# SMPS.net
KiCad netlist of a schematic drawn in Altium Designer
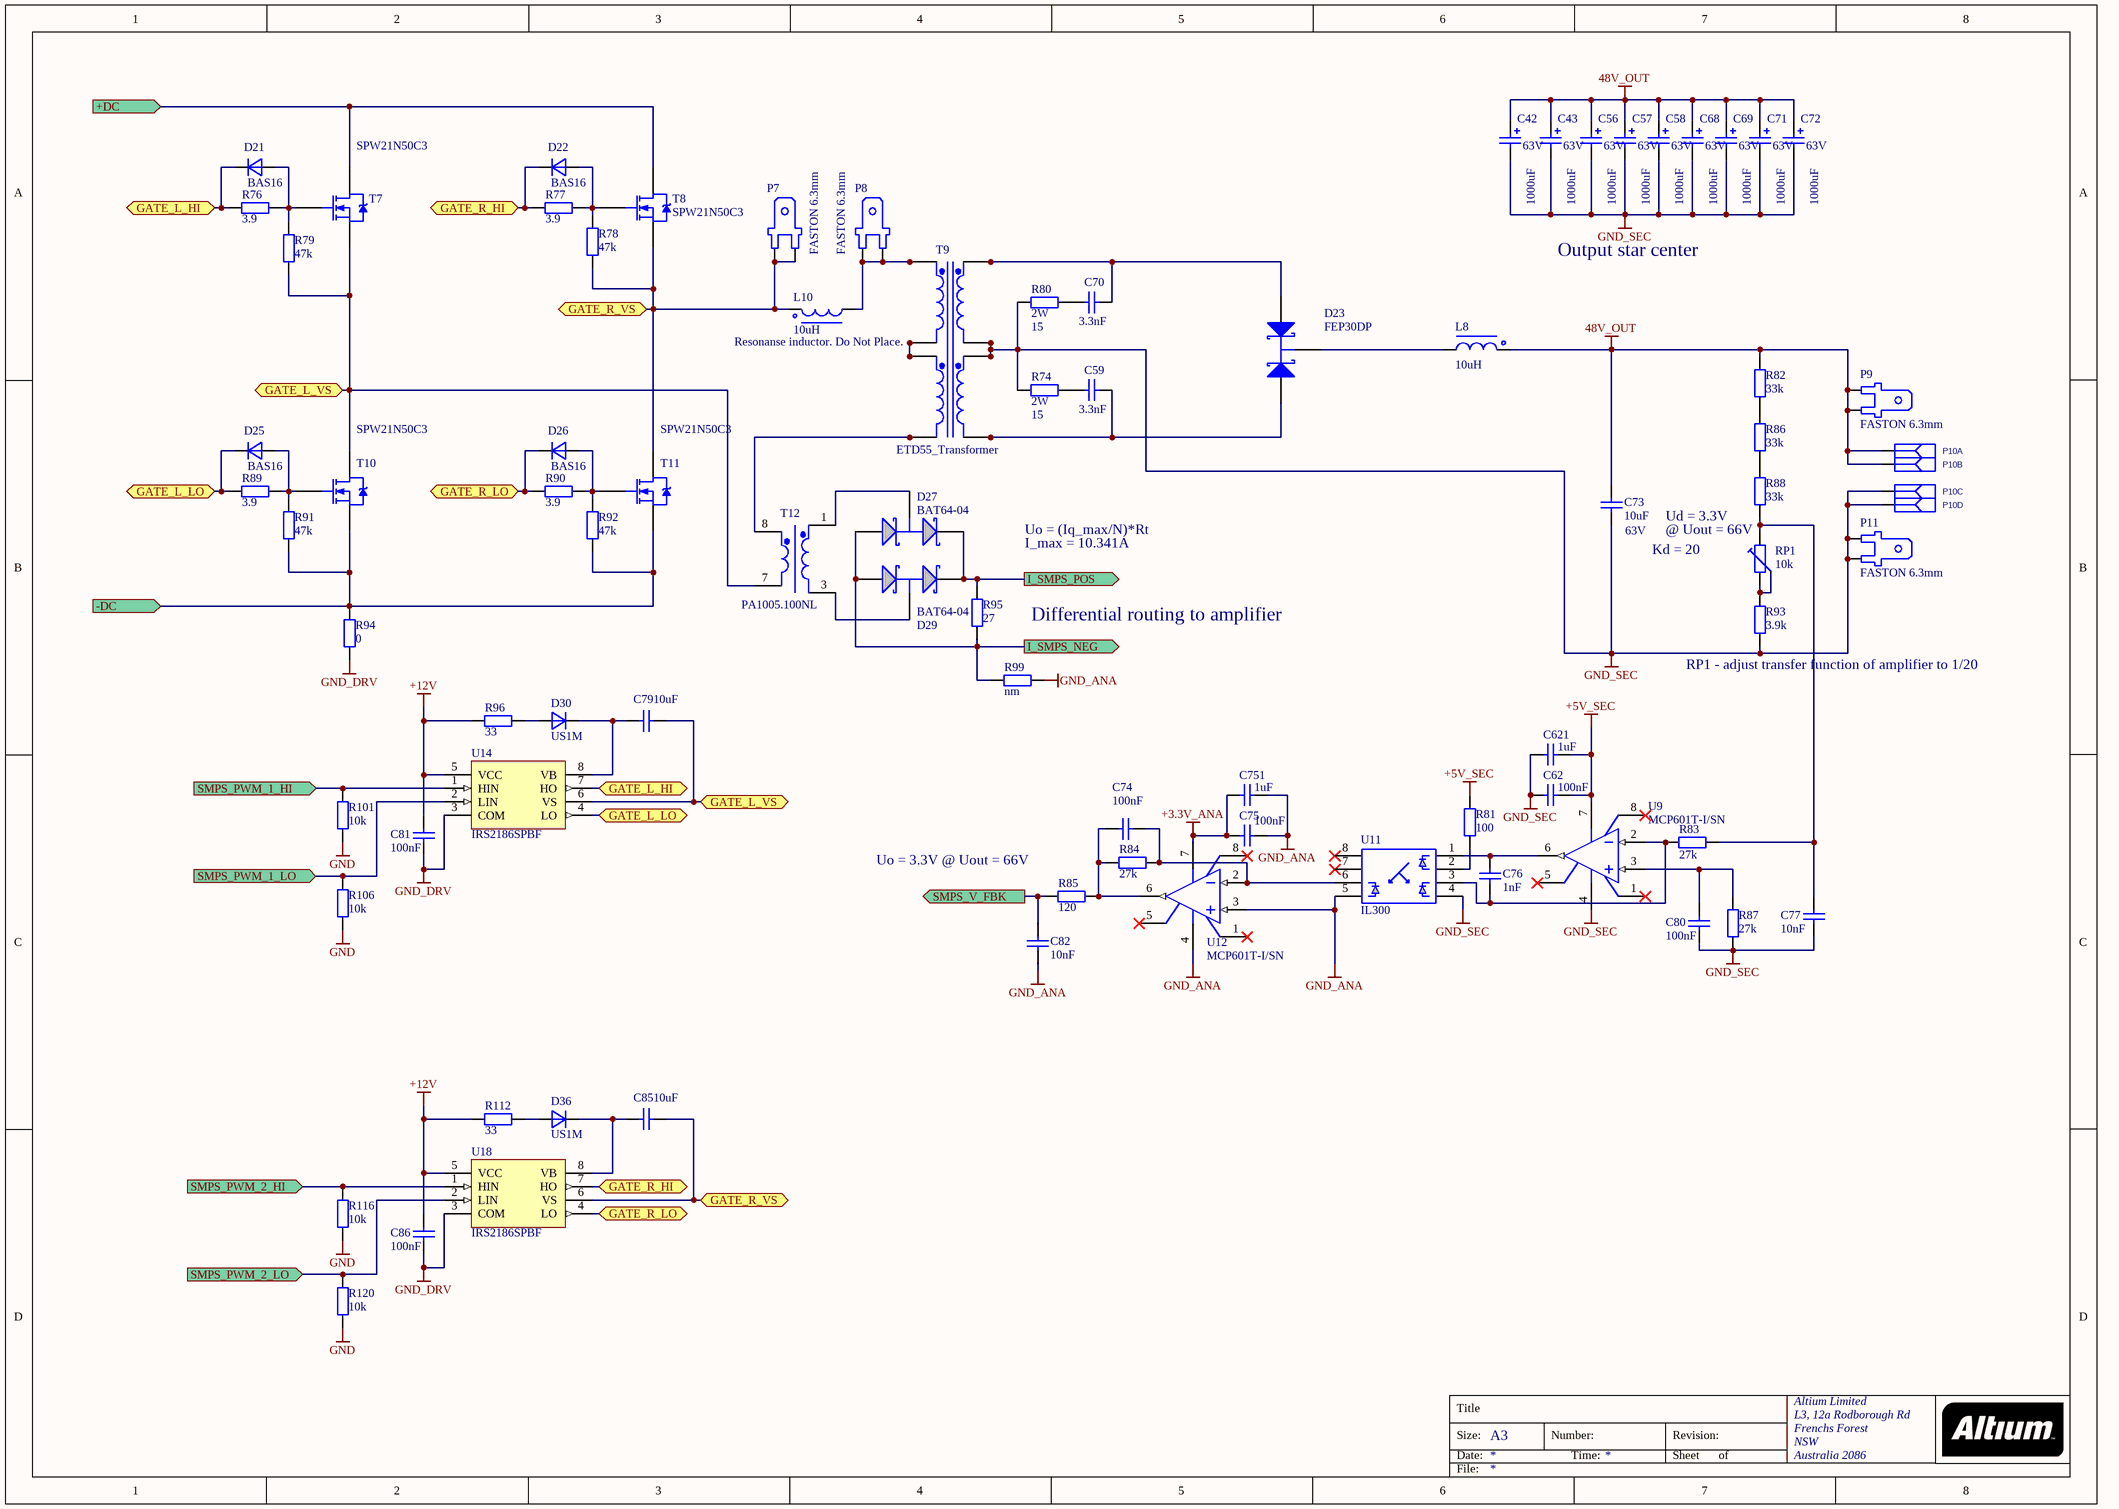
[diagram p0: SMPS.SchDoc]

(export (version "E")
  (design (tool "Eeschema 10.0.6"))
  (components
    (comp (ref "C42")
      (value "1000uF")
      (footprint "CAPPR7.5-18x35.5")
      (fields (field (name "VOLTAGE") "63V") (field (name "Comment") "Cap"))
      (libsource (lib "Capacitors") (part "Cap pol"))
    )
    (comp (ref "C43")
      (value "1000uF")
      (footprint "CAPPR7.5-18x35.5")
      (fields (field (name "VOLTAGE") "63V") (field (name "Comment") "Cap"))
      (libsource (lib "Capacitors") (part "Cap pol"))
    )
    (comp (ref "C56")
      (value "1000uF")
      (footprint "CAPPR7.5-18x35.5")
      (fields (field (name "VOLTAGE") "63V") (field (name "Comment") "Cap"))
      (libsource (lib "Capacitors") (part "Cap pol"))
    )
    (comp (ref "C57")
      (value "1000uF")
      (footprint "CAPPR7.5-18x35.5")
      (fields (field (name "VOLTAGE") "63V") (field (name "Comment") "Cap"))
      (libsource (lib "Capacitors") (part "Cap pol"))
    )
    (comp (ref "C58")
      (value "1000uF")
      (footprint "CAPPR7.5-18x35.5")
      (fields (field (name "VOLTAGE") "63V") (field (name "Comment") "Cap"))
      (libsource (lib "Capacitors") (part "Cap pol"))
    )
    (comp (ref "C59")
      (value "3.3nF")
      (footprint "CAP26X19P22_5H")
      (fields (field (name "Comment") "Cap"))
      (libsource (lib "Capacitors") (part "Cap"))
    )
    (comp (ref "C62")
      (value "100nF")
      (footprint "1206_REFLOW")
      (fields (field (name "Comment") "Cap 1206"))
      (libsource (lib "Capacitors") (part "Cap 1206"))
    )
    (comp (ref "C68")
      (value "1000uF")
      (footprint "CAPPR7.5-18x35.5")
      (fields (field (name "VOLTAGE") "63V") (field (name "Comment") "Cap"))
      (libsource (lib "Capacitors") (part "Cap pol"))
    )
    (comp (ref "C69")
      (value "1000uF")
      (footprint "CAPPR7.5-18x35.5")
      (fields (field (name "VOLTAGE") "63V") (field (name "Comment") "Cap"))
      (libsource (lib "Capacitors") (part "Cap pol"))
    )
    (comp (ref "C70")
      (value "3.3nF")
      (footprint "CAP26X19P22_5H")
      (fields (field (name "Comment") "Cap"))
      (libsource (lib "Capacitors") (part "Cap"))
    )
    (comp (ref "C71")
      (value "1000uF")
      (footprint "CAPPR7.5-18x35.5")
      (fields (field (name "VOLTAGE") "63V") (field (name "Comment") "Cap"))
      (libsource (lib "Capacitors") (part "Cap pol"))
    )
    (comp (ref "C72")
      (value "1000uF")
      (footprint "CAPPR7.5-18x35.5")
      (fields (field (name "VOLTAGE") "63V") (field (name "Comment") "Cap"))
      (libsource (lib "Capacitors") (part "Cap pol"))
    )
    (comp (ref "C73")
      (value "10uF")
      (footprint "RECT 26.5X8.5 RM22.5")
      (fields
        (field (name "VOLTAGE") "63V")
        (field (name "MANUFACTURER") "WIMA")
        (field (name "Comment") "Cap")
      )
      (libsource (lib "Capacitors") (part "Cap"))
    )
    (comp (ref "C74")
      (value "100nF")
      (footprint "1206_REFLOW")
      (fields (field (name "Comment") "Cap 1206"))
      (libsource (lib "Capacitors") (part "Cap 1206"))
    )
    (comp (ref "C75")
      (value "100nF")
      (footprint "1206_REFLOW")
      (fields (field (name "Comment") "Cap 1206"))
      (libsource (lib "Capacitors") (part "Cap 1206"))
    )
    (comp (ref "C76")
      (value "1nF")
      (footprint "1206_REFLOW")
      (fields (field (name "Comment") "Cap 1206"))
      (libsource (lib "Capacitors") (part "Cap 1206"))
    )
    (comp (ref "C77")
      (value "10nF")
      (footprint "1206_REFLOW")
      (fields (field (name "Comment") "Cap 1206"))
      (libsource (lib "Capacitors") (part "Cap 1206"))
    )
    (comp (ref "C79")
      (value "10uF")
      (footprint "1206_REFLOW")
      (fields (field (name "Comment") "Cap 1206"))
      (libsource (lib "Capacitors") (part "Cap 1206"))
    )
    (comp (ref "C80")
      (value "100nF")
      (footprint "1206_REFLOW")
      (fields (field (name "Comment") "Cap 1206"))
      (libsource (lib "Capacitors") (part "Cap 1206"))
    )
    (comp (ref "C81")
      (value "100nF")
      (footprint "1206_REFLOW")
      (fields (field (name "Comment") "Cap 1206"))
      (libsource (lib "Capacitors") (part "Cap 1206"))
    )
    (comp (ref "C82")
      (value "10nF")
      (footprint "1206_REFLOW")
      (fields (field (name "Comment") "Cap"))
      (libsource (lib "Capacitors") (part "Cap"))
    )
    (comp (ref "C85")
      (value "10uF")
      (footprint "1206_REFLOW")
      (fields (field (name "Comment") "Cap 1206"))
      (libsource (lib "Capacitors") (part "Cap 1206"))
    )
    (comp (ref "C86")
      (value "100nF")
      (footprint "1206_REFLOW")
      (fields (field (name "Comment") "Cap 1206"))
      (libsource (lib "Capacitors") (part "Cap 1206"))
    )
    (comp (ref "C621")
      (value "1uF")
      (footprint "1206_REFLOW")
      (fields (field (name "Comment") "Cap 1206"))
      (libsource (lib "Capacitors") (part "Cap 1206"))
    )
    (comp (ref "C751")
      (value "1uF")
      (footprint "1206_REFLOW")
      (fields (field (name "Comment") "Cap 1206"))
      (libsource (lib "Capacitors") (part "Cap 1206"))
    )
    (comp (ref "D21")
      (value "BAS16")
      (footprint "SOT23_HIS_Primary")
      (description "DIODE, SINGLE SOT-23")
      (fields (field (name "MANUFACTURER") "Any"))
      (libsource (lib "Diode") (part "BAS16"))
    )
    (comp (ref "D22")
      (value "BAS16")
      (footprint "SOT23_HIS_Primary")
      (description "DIODE, SINGLE SOT-23")
      (fields (field (name "MANUFACTURER") "Any"))
      (libsource (lib "Diode") (part "BAS16"))
    )
    (comp (ref "D23")
      (value "FEP30DP")
      (footprint "TO-247HV")
      (description "Schottky Rectifier")
      (fields
        (field (name "MANUFACTURER") "VISHAY GENERAL SEMICONDUCTOR")
        (field (name "Comment") "DIODE, ULTRAFAST, 30 A, TO-3P")
      )
      (libsource (lib "Diode") (part "FEP30DP"))
    )
    (comp (ref "D25")
      (value "BAS16")
      (footprint "SOT23_HIS_Primary")
      (description "DIODE, SINGLE SOT-23")
      (fields (field (name "MANUFACTURER") "Any"))
      (libsource (lib "Diode") (part "BAS16"))
    )
    (comp (ref "D26")
      (value "BAS16")
      (footprint "SOT23_HIS_Primary")
      (description "DIODE, SINGLE SOT-23")
      (fields (field (name "MANUFACTURER") "Any"))
      (libsource (lib "Diode") (part "BAS16"))
    )
    (comp (ref "D27")
      (value "BAT64-04")
      (footprint "SOT23_HIS_Primary")
      (description "Silicon Schottky Diodes")
      (fields (field (name "MANUFACTURER") "INF") (field (name "PUBLISHER") "Altium Limited"))
      (libsource (lib "") (part "BAT64-04_1"))
    )
    (comp (ref "D29")
      (value "BAT64-04")
      (footprint "SOT23_HIS_Primary")
      (description "Silicon Schottky Diodes")
      (fields (field (name "MANUFACTURER") "INF") (field (name "PUBLISHER") "Altium Limited"))
      (libsource (lib "Diode") (part "BAT64-04"))
    )
    (comp (ref "D30") (value "US1M") (footprint "DO-214_S1A(Primary)") (libsource (lib "Diode") (part "S1A")))
    (comp (ref "D36") (value "US1M") (footprint "DO-214_S1A(Primary)") (libsource (lib "Diode") (part "S1A")))
    (comp (ref "L8")
      (value "10uH")
      (footprint "BOURNS - SRP1270-100M")
      (description "BOURNS - SRP1270-100M - INDUCTOR, SMD, 10UH, 16A")
      (fields (field (name "MANUFACTURER") "Bourns") (field (name "Comment") "SRP1270-100M"))
      (libsource (lib "Inductor") (part "BOURNS - SRP1270-xxxM"))
    )
    (comp (ref "L10")
      (value "Resonanse inductor. Do Not Place.")
      (footprint "BOURNS - SRP1270-100M")
      (description "BOURNS - SRP1270-100M - INDUCTOR, SMD, 10UH, 16A")
      (fields (field (name "MANUFACTURER") "Bourns") (field (name "ALTIUM_VALUE") "10uH"))
      (libsource (lib "Inductor") (part "BOURNS - SRP1270-xxxM"))
    )
    (comp (ref "P7")
      (value "FASTON 6.3mm")
      (footprint "FASTON 6.3mm")
      (fields (field (name "Comment") "FASTON 6.3MM"))
      (libsource (lib "Connector") (part "FASTON 6.3MM"))
    )
    (comp (ref "P8")
      (value "FASTON 6.3mm")
      (footprint "FASTON 6.3mm")
      (fields (field (name "Comment") "FASTON 6.3MM"))
      (libsource (lib "Connector") (part "FASTON 6.3MM"))
    )
    (comp (ref "P9")
      (value "FASTON 6.3mm")
      (footprint "FASTON 6.3mm")
      (fields (field (name "Comment") "FASTON 6.3MM"))
      (libsource (lib "Connector") (part "FASTON 6.3MM"))
    )
    (comp (ref "P10")
      (value "MSTBA 2,5/ 4-G-5,08")
      (footprint "MSTBA2.5/4G-5.08")
      (description "Header, right angled, 12 A, 250 V, pitch 5.08 mm, No. of poles:4")
      (fields (field (name "MANUFACTURER") "Phoenix") (field (name "MFRR. PART NO.") "1757268"))
      (libsource (lib "Connector IDS") (part "MSTBA 2,5/ 4-G-5,08"))
    )
    (comp (ref "P11")
      (value "FASTON 6.3mm")
      (footprint "FASTON 6.3mm")
      (fields (field (name "Comment") "FASTON 6.3MM"))
      (libsource (lib "Connector") (part "FASTON 6.3MM"))
    )
    (comp (ref "R74")
      (value "2W")
      (footprint "5.5x16mm (2W BODY RES)")
      (fields (field (name "ALTIUM_VALUE") "15"))
      (libsource (lib "") (part "RES 1_2"))
    )
    (comp (ref "R76")
      (value "3.9")
      (footprint "1206_REFLOW")
      (fields (field (name "Comment") "RES"))
      (libsource (lib "Resistor") (part "RES 1"))
    )
    (comp (ref "R77")
      (value "3.9")
      (footprint "1206_REFLOW")
      (fields (field (name "Comment") "RES"))
      (libsource (lib "") (part "RES 1_2"))
    )
    (comp (ref "R78")
      (value "47k")
      (footprint "1206_REFLOW")
      (fields (field (name "Comment") "RES"))
      (libsource (lib "") (part "RES 1_1"))
    )
    (comp (ref "R79")
      (value "47k")
      (footprint "1206_REFLOW")
      (fields (field (name "Comment") "RES"))
      (libsource (lib "") (part "RES 1_3"))
    )
    (comp (ref "R80")
      (value "2W")
      (footprint "5.5x16mm (2W BODY RES)")
      (fields (field (name "ALTIUM_VALUE") "15"))
      (libsource (lib "") (part "RES 1_2"))
    )
    (comp (ref "R81")
      (value "100")
      (footprint "1206_REFLOW")
      (fields (field (name "Comment") "RES"))
      (libsource (lib "") (part "RES 1_1"))
    )
    (comp (ref "R82")
      (value "33k")
      (footprint "1206_REFLOW")
      (fields (field (name "TOLERANCE") "1%") (field (name "Comment") "RES"))
      (libsource (lib "") (part "RES 1_1"))
    )
    (comp (ref "R83")
      (value "27k")
      (footprint "1206_REFLOW")
      (fields (field (name "Comment") "RES"))
      (libsource (lib "Resistor") (part "RES 1"))
    )
    (comp (ref "R84")
      (value "27k")
      (footprint "1206_REFLOW")
      (fields (field (name "Comment") "RES"))
      (libsource (lib "Resistor") (part "RES 1"))
    )
    (comp (ref "R85")
      (value "120")
      (footprint "1206_REFLOW")
      (fields (field (name "Comment") "RES"))
      (libsource (lib "Resistor") (part "RES 1"))
    )
    (comp (ref "R86")
      (value "33k")
      (footprint "1206_REFLOW")
      (fields (field (name "TOLERANCE") "1%") (field (name "Comment") "RES"))
      (libsource (lib "") (part "RES 1_1"))
    )
    (comp (ref "R87")
      (value "27k")
      (footprint "1206_REFLOW")
      (fields (field (name "Comment") "RES"))
      (libsource (lib "") (part "RES 1_1"))
    )
    (comp (ref "R88")
      (value "33k")
      (footprint "1206_REFLOW")
      (fields (field (name "TOLERANCE") "1%") (field (name "Comment") "RES"))
      (libsource (lib "") (part "RES 1_1"))
    )
    (comp (ref "R89")
      (value "3.9")
      (footprint "1206_REFLOW")
      (fields (field (name "Comment") "RES"))
      (libsource (lib "") (part "RES 1_2"))
    )
    (comp (ref "R90")
      (value "3.9")
      (footprint "1206_REFLOW")
      (fields (field (name "Comment") "RES"))
      (libsource (lib "Resistor") (part "RES 1"))
    )
    (comp (ref "R91")
      (value "47k")
      (footprint "1206_REFLOW")
      (fields (field (name "Comment") "RES"))
      (libsource (lib "") (part "RES 1_1"))
    )
    (comp (ref "R92")
      (value "47k")
      (footprint "1206_REFLOW")
      (fields (field (name "Comment") "RES"))
      (libsource (lib "") (part "RES 1_3"))
    )
    (comp (ref "R93")
      (value "3.9k")
      (footprint "1206_REFLOW")
      (fields (field (name "TOLERANCE") "1%") (field (name "Comment") "RES"))
      (libsource (lib "") (part "RES 1_1"))
    )
    (comp (ref "R94")
      (value "0")
      (footprint "1206_REFLOW")
      (fields (field (name "Comment") "RES"))
      (libsource (lib "") (part "RES 1_1"))
    )
    (comp (ref "R95")
      (value "27")
      (footprint "1206_REFLOW")
      (fields (field (name "Comment") "RES"))
      (libsource (lib "") (part "RES 1_1"))
    )
    (comp (ref "R96")
      (value "33")
      (footprint "1206_REFLOW")
      (fields (field (name "Comment") "RES"))
      (libsource (lib "Resistor") (part "RES 1"))
    )
    (comp (ref "R99")
      (value "nm")
      (footprint "1206_REFLOW")
      (fields (field (name "Comment") "RES"))
      (libsource (lib "Resistor") (part "RES 1"))
    )
    (comp (ref "R101")
      (value "10k")
      (footprint "1206_REFLOW")
      (fields (field (name "Comment") "RES"))
      (libsource (lib "") (part "RES 1_3"))
    )
    (comp (ref "R106")
      (value "10k")
      (footprint "1206_REFLOW")
      (fields (field (name "Comment") "RES"))
      (libsource (lib "") (part "RES 1_3"))
    )
    (comp (ref "R112")
      (value "33")
      (footprint "1206_REFLOW")
      (fields (field (name "Comment") "RES"))
      (libsource (lib "Resistor") (part "RES 1"))
    )
    (comp (ref "R116")
      (value "10k")
      (footprint "1206_REFLOW")
      (fields (field (name "Comment") "RES"))
      (libsource (lib "") (part "RES 1_3"))
    )
    (comp (ref "R120")
      (value "10k")
      (footprint "1206_REFLOW")
      (fields (field (name "Comment") "RES"))
      (libsource (lib "") (part "RES 1_3"))
    )
    (comp (ref "RP1")
      (value "10k")
      (footprint "BOURNS3296W")
      (fields (field (name "Comment") "Trimmer"))
      (libsource (lib "Resistor") (part "Res Trim"))
    )
    (comp (ref "T7")
      (value "SPW21N50C3")
      (footprint "TO-247HV")
      (description "INFINEON - SPW21N50C3 - MOSFET, N, 500V, TO-247")
      (fields (field (name "Comment") "MOSFET, N, 500V, TO-247"))
      (libsource (lib "Transistors") (part "SPW21N50C3"))
    )
    (comp (ref "T8")
      (value "SPW21N50C3")
      (footprint "TO-247HV")
      (description "INFINEON - SPW21N50C3 - MOSFET, N, 500V, TO-247")
      (fields (field (name "Comment") "MOSFET, N, 500V, TO-247"))
      (libsource (lib "Transistors") (part "SPW21N50C3"))
    )
    (comp (ref "T9")
      (value "ETD55_Transformer")
      (footprint "ETD54_Transformer")
      (libsource (lib "Transformer") (part "ETD55_Transformer"))
    )
    (comp (ref "T10")
      (value "SPW21N50C3")
      (footprint "TO-247HV")
      (description "INFINEON - SPW21N50C3 - MOSFET, N, 500V, TO-247")
      (fields (field (name "Comment") "MOSFET, N, 500V, TO-247"))
      (libsource (lib "Transistors") (part "SPW21N50C3"))
    )
    (comp (ref "T11")
      (value "SPW21N50C3")
      (footprint "TO-247HV")
      (description "INFINEON - SPW21N50C3 - MOSFET, N, 500V, TO-247")
      (fields (field (name "Comment") "MOSFET, N, 500V, TO-247"))
      (libsource (lib "Transistors") (part "SPW21N50C3"))
    )
    (comp (ref "T12")
      (value "PA1005.100NL")
      (footprint "PA1005.XXXNL Series")
      (fields
        (field (name "MANUFACTURER") "PULSE ELECTRONICS CORPORATION")
        (field (name "Comment") "PA1005.XXXNL")
      )
      (libsource (lib "Transformer") (part "PA1005.XXXNL Series"))
    )
    (comp (ref "U9")
      (value "MCP601T-I/SN")
      (footprint "SOIC-SN8_N")
      (fields (field (name "PUBLISHER") "Altium Limited"))
      (libsource (lib "Microchip Linear Devices") (part "MCP601T-I/SN"))
    )
    (comp (ref "U11")
      (value "IL300")
      (footprint "DIP8 6n138")
      (fields (field (name "Comment") "Analog optocoupler"))
      (libsource (lib "Optocoupler") (part "IL300"))
    )
    (comp (ref "U12")
      (value "MCP601T-I/SN")
      (footprint "SOIC-SN8_N")
      (fields (field (name "PUBLISHER") "Altium Limited"))
      (libsource (lib "Microchip Linear Devices") (part "MCP601T-I/SN"))
    )
    (comp (ref "U14")
      (value "IRS2186SPBF")
      (footprint "SO-8_N")
      (description "Half-Bridge Driver")
      (fields (field (name "PUBLISHER") "Altium Limited"))
      (libsource (lib "IR Interface Bridge Driver") (part "IRS2186SPBF"))
    )
    (comp (ref "U18")
      (value "IRS2186SPBF")
      (footprint "SO-8_N")
      (description "Half-Bridge Driver")
      (fields (field (name "PUBLISHER") "Altium Limited"))
      (libsource (lib "IR Interface Bridge Driver") (part "IRS2186SPBF"))
    )
  )
  (nets
    (net (code "1") (name "+3.3V_ANA") (class "Default")
      (node (ref "C75") (pin "1") (pinfunction "1_1") (pintype "passive"))
      (node (ref "C751") (pin "1") (pinfunction "1_1") (pintype "passive"))
      (node (ref "U12") (pin "7") (pinfunction "VDD_7") (pintype "power_in"))
    )
    (net (code "2") (name "+5V_SEC") (class "Default")
      (node (ref "C62") (pin "2") (pinfunction "2_2") (pintype "passive"))
      (node (ref "C621") (pin "2") (pinfunction "2_2") (pintype "passive"))
      (node (ref "R81") (pin "1") (pinfunction "1_1") (pintype "passive"))
      (node (ref "U9") (pin "7") (pinfunction "VDD_7") (pintype "power_in"))
    )
    (net (code "3") (name "+12V") (class "Default")
      (node (ref "C81") (pin "1") (pinfunction "1_1") (pintype "passive"))
      (node (ref "C86") (pin "1") (pinfunction "1_1") (pintype "passive"))
      (node (ref "R112") (pin "1") (pinfunction "1_1") (pintype "passive"))
      (node (ref "R96") (pin "1") (pinfunction "1_1") (pintype "passive"))
      (node (ref "U14") (pin "5") (pinfunction "VCC_5") (pintype "power_in"))
      (node (ref "U18") (pin "5") (pinfunction "VCC_5") (pintype "power_in"))
    )
    (net (code "4") (name "/+DC") (class "Default")
      (node (ref "T7") (pin "2") (pinfunction "D_2") (pintype "passive"))
      (node (ref "T8") (pin "2") (pinfunction "D_2") (pintype "passive"))
    )
    (net (code "5") (name "/-DC") (class "Default")
      (node (ref "R91") (pin "2") (pinfunction "2_2") (pintype "passive"))
      (node (ref "R92") (pin "1") (pinfunction "1_1") (pintype "passive"))
      (node (ref "R94") (pin "1") (pinfunction "1_1") (pintype "passive"))
      (node (ref "T10") (pin "3") (pinfunction "S_3") (pintype "passive"))
      (node (ref "T11") (pin "3") (pinfunction "S_3") (pintype "passive"))
    )
    (net (code "6") (name "/GATE_L_HI") (class "Default")
      (node (ref "D21") (pin "3") (pinfunction "K_3") (pintype "passive"))
      (node (ref "R76") (pin "1") (pinfunction "1_1") (pintype "passive"))
      (node (ref "U14") (pin "7") (pinfunction "HO_7") (pintype "output"))
    )
    (net (code "7") (name "/GATE_L_LO") (class "Default")
      (node (ref "D25") (pin "3") (pinfunction "K_3") (pintype "passive"))
      (node (ref "R89") (pin "2") (pinfunction "2_2") (pintype "passive"))
      (node (ref "U14") (pin "4") (pinfunction "LO_4") (pintype "output"))
    )
    (net (code "8") (name "/GATE_L_VS") (class "Default")
      (node (ref "C79") (pin "1") (pinfunction "1_1") (pintype "passive"))
      (node (ref "R79") (pin "1") (pinfunction "1_1") (pintype "passive"))
      (node (ref "T10") (pin "2") (pinfunction "D_2") (pintype "passive"))
      (node (ref "T12") (pin "7") (pinfunction "Pri-_7") (pintype "passive"))
      (node (ref "T7") (pin "3") (pinfunction "S_3") (pintype "passive"))
      (node (ref "U14") (pin "6") (pinfunction "VS_6") (pintype "power_in"))
    )
    (net (code "9") (name "/GATE_R_HI") (class "Default")
      (node (ref "D22") (pin "3") (pinfunction "K_3") (pintype "passive"))
      (node (ref "R77") (pin "2") (pinfunction "2_2") (pintype "passive"))
      (node (ref "U18") (pin "7") (pinfunction "HO_7") (pintype "output"))
    )
    (net (code "10") (name "/GATE_R_LO") (class "Default")
      (node (ref "D26") (pin "3") (pinfunction "K_3") (pintype "passive"))
      (node (ref "R90") (pin "1") (pinfunction "1_1") (pintype "passive"))
      (node (ref "U18") (pin "4") (pinfunction "LO_4") (pintype "output"))
    )
    (net (code "11") (name "/GATE_R_VS") (class "Default")
      (node (ref "C85") (pin "1") (pinfunction "1_1") (pintype "passive"))
      (node (ref "L10") (pin "2") (pinfunction "2_2") (pintype "passive"))
      (node (ref "P7") (pin "1") (pinfunction "1_1") (pintype "passive"))
      (node (ref "P7") (pin "2") (pinfunction "2_2") (pintype "passive"))
      (node (ref "R78") (pin "2") (pinfunction "2_2") (pintype "passive"))
      (node (ref "T11") (pin "2") (pinfunction "D_2") (pintype "passive"))
      (node (ref "T8") (pin "3") (pinfunction "S_3") (pintype "passive"))
      (node (ref "U18") (pin "6") (pinfunction "VS_6") (pintype "power_in"))
    )
    (net (code "12") (name "/I_SMPS_NEG") (class "Default")
      (node (ref "D27") (pin "1") (pinfunction "A_1") (pintype "passive"))
      (node (ref "D29") (pin "1") (pinfunction "A_1") (pintype "passive"))
      (node (ref "R95") (pin "2") (pinfunction "2_2") (pintype "passive"))
      (node (ref "R99") (pin "1") (pinfunction "1_1") (pintype "passive"))
    )
    (net (code "13") (name "/I_SMPS_POS") (class "Default")
      (node (ref "D27") (pin "2") (pinfunction "K_2") (pintype "passive"))
      (node (ref "D29") (pin "2") (pinfunction "K_2") (pintype "passive"))
      (node (ref "R95") (pin "1") (pinfunction "1_1") (pintype "passive"))
    )
    (net (code "14") (name "/SMPS_PWM_1_HI") (class "Default")
      (node (ref "R101") (pin "2") (pinfunction "2_2") (pintype "passive"))
      (node (ref "U14") (pin "1") (pinfunction "HIN_1") (pintype "input"))
    )
    (net (code "15") (name "/SMPS_PWM_1_LO") (class "Default")
      (node (ref "R106") (pin "2") (pinfunction "2_2") (pintype "passive"))
      (node (ref "U14") (pin "2") (pinfunction "LIN_2") (pintype "input"))
    )
    (net (code "16") (name "/SMPS_PWM_2_HI") (class "Default")
      (node (ref "R116") (pin "2") (pinfunction "2_2") (pintype "passive"))
      (node (ref "U18") (pin "1") (pinfunction "HIN_1") (pintype "input"))
    )
    (net (code "17") (name "/SMPS_PWM_2_LO") (class "Default")
      (node (ref "R120") (pin "2") (pinfunction "2_2") (pintype "passive"))
      (node (ref "U18") (pin "2") (pinfunction "LIN_2") (pintype "input"))
    )
    (net (code "18") (name "/SMPS_V_FBK") (class "Default")
      (node (ref "C82") (pin "2") (pinfunction "2_2") (pintype "passive"))
      (node (ref "R85") (pin "1") (pinfunction "1_1") (pintype "passive"))
    )
    (net (code "19") (name "48V_OUT") (class "Default")
      (node (ref "C42") (pin "1") (pinfunction "1_1") (pintype "passive"))
      (node (ref "C43") (pin "1") (pinfunction "1_1") (pintype "passive"))
      (node (ref "C56") (pin "1") (pinfunction "1_1") (pintype "passive"))
      (node (ref "C57") (pin "1") (pinfunction "1_1") (pintype "passive"))
      (node (ref "C58") (pin "1") (pinfunction "1_1") (pintype "passive"))
      (node (ref "C68") (pin "1") (pinfunction "1_1") (pintype "passive"))
      (node (ref "C69") (pin "1") (pinfunction "1_1") (pintype "passive"))
      (node (ref "C71") (pin "1") (pinfunction "1_1") (pintype "passive"))
      (node (ref "C72") (pin "1") (pinfunction "1_1") (pintype "passive"))
      (node (ref "C73") (pin "2") (pinfunction "2_2") (pintype "passive"))
      (node (ref "L8") (pin "2") (pinfunction "2_2") (pintype "passive"))
      (node (ref "P10") (pin "1") (pinfunction "SIG_1") (pintype "passive"))
      (node (ref "P10") (pin "2") (pinfunction "SIG_2") (pintype "passive"))
      (node (ref "P9") (pin "1") (pinfunction "1_1") (pintype "passive"))
      (node (ref "P9") (pin "2") (pinfunction "2_2") (pintype "passive"))
      (node (ref "R82") (pin "1") (pinfunction "1_1") (pintype "passive"))
    )
    (net (code "20") (name "GND") (class "Default")
      (node (ref "R101") (pin "1") (pinfunction "1_1") (pintype "passive"))
      (node (ref "R106") (pin "1") (pinfunction "1_1") (pintype "passive"))
      (node (ref "R116") (pin "1") (pinfunction "1_1") (pintype "passive"))
      (node (ref "R120") (pin "1") (pinfunction "1_1") (pintype "passive"))
    )
    (net (code "21") (name "GND_ANA") (class "Default")
      (node (ref "C75") (pin "2") (pinfunction "2_2") (pintype "passive"))
      (node (ref "C751") (pin "2") (pinfunction "2_2") (pintype "passive"))
      (node (ref "C82") (pin "1") (pinfunction "1_1") (pintype "passive"))
      (node (ref "R99") (pin "2") (pinfunction "2_2") (pintype "passive"))
      (node (ref "U11") (pin "5") (pinfunction "GND_5") (pintype "passive"))
      (node (ref "U12") (pin "3") (pinfunction "VIN+_3") (pintype "input"))
      (node (ref "U12") (pin "4") (pinfunction "VSS_4") (pintype "power_in"))
    )
    (net (code "22") (name "GND_DRV") (class "Default")
      (node (ref "C81") (pin "2") (pinfunction "2_2") (pintype "passive"))
      (node (ref "C86") (pin "2") (pinfunction "2_2") (pintype "passive"))
      (node (ref "R94") (pin "2") (pinfunction "2_2") (pintype "passive"))
      (node (ref "U14") (pin "3") (pinfunction "COM_3") (pintype "power_in"))
      (node (ref "U18") (pin "3") (pinfunction "COM_3") (pintype "power_in"))
    )
    (net (code "23") (name "GND_SEC") (class "Default")
      (node (ref "C42") (pin "2") (pinfunction "2_2") (pintype "passive"))
      (node (ref "C43") (pin "2") (pinfunction "2_2") (pintype "passive"))
      (node (ref "C56") (pin "2") (pinfunction "2_2") (pintype "passive"))
      (node (ref "C57") (pin "2") (pinfunction "2_2") (pintype "passive"))
      (node (ref "C58") (pin "2") (pinfunction "2_2") (pintype "passive"))
      (node (ref "C62") (pin "1") (pinfunction "1_1") (pintype "passive"))
      (node (ref "C621") (pin "1") (pinfunction "1_1") (pintype "passive"))
      (node (ref "C68") (pin "2") (pinfunction "2_2") (pintype "passive"))
      (node (ref "C69") (pin "2") (pinfunction "2_2") (pintype "passive"))
      (node (ref "C71") (pin "2") (pinfunction "2_2") (pintype "passive"))
      (node (ref "C72") (pin "2") (pinfunction "2_2") (pintype "passive"))
      (node (ref "C73") (pin "1") (pinfunction "1_1") (pintype "passive"))
      (node (ref "C77") (pin "1") (pinfunction "1_1") (pintype "passive"))
      (node (ref "C80") (pin "1") (pinfunction "1_1") (pintype "passive"))
      (node (ref "P10") (pin "3") (pinfunction "SIG_3") (pintype "passive"))
      (node (ref "P10") (pin "4") (pinfunction "SIG_4") (pintype "passive"))
      (node (ref "P11") (pin "1") (pinfunction "1_1") (pintype "passive"))
      (node (ref "P11") (pin "2") (pinfunction "2_2") (pintype "passive"))
      (node (ref "R74") (pin "2") (pinfunction "2_2") (pintype "passive"))
      (node (ref "R80") (pin "2") (pinfunction "2_2") (pintype "passive"))
      (node (ref "R87") (pin "2") (pinfunction "2_2") (pintype "passive"))
      (node (ref "R93") (pin "2") (pinfunction "2_2") (pintype "passive"))
      (node (ref "T9") (pin "14") (pinfunction "Sec2+_14") (pintype "passive"))
      (node (ref "T9") (pin "15") (pinfunction "Sec2+_15") (pintype "passive"))
      (node (ref "T9") (pin "19") (pinfunction "Sec2+_19") (pintype "passive"))
      (node (ref "T9") (pin "20") (pinfunction "Sec2+_20") (pintype "passive"))
      (node (ref "U11") (pin "4") (pinfunction "4_4") (pintype "passive"))
      (node (ref "U9") (pin "4") (pinfunction "VSS_4") (pintype "power_in"))
    )
    (net (code "24") (name "Net-(C59-Pad1)") (class "Default")
      (node (ref "C59") (pin "1") (pinfunction "1_1") (pintype "passive"))
      (node (ref "R74") (pin "1") (pinfunction "1_1") (pintype "passive"))
    )
    (net (code "25") (name "Net-(C70-Pad1)") (class "Default")
      (node (ref "C70") (pin "1") (pinfunction "1_1") (pintype "passive"))
      (node (ref "R80") (pin "1") (pinfunction "1_1") (pintype "passive"))
    )
    (net (code "26") (name "Net-(C77-Pad2)") (class "Default")
      (node (ref "C77") (pin "2") (pinfunction "2_2") (pintype "passive"))
      (node (ref "R83") (pin "2") (pinfunction "2_2") (pintype "passive"))
      (node (ref "R88") (pin "2") (pinfunction "2_2") (pintype "passive"))
      (node (ref "RP1") (pin "3") (pinfunction "3_3") (pintype "passive"))
    )
    (net (code "27") (name "Net-(D21-A)") (class "Default")
      (node (ref "D21") (pin "1") (pinfunction "A_1") (pintype "passive"))
      (node (ref "R76") (pin "2") (pinfunction "2_2") (pintype "passive"))
      (node (ref "R79") (pin "2") (pinfunction "2_2") (pintype "passive"))
      (node (ref "T7") (pin "1") (pinfunction "G_1") (pintype "passive"))
    )
    (net (code "28") (name "Net-(D22-A)") (class "Default")
      (node (ref "D22") (pin "1") (pinfunction "A_1") (pintype "passive"))
      (node (ref "R77") (pin "1") (pinfunction "1_1") (pintype "passive"))
      (node (ref "R78") (pin "1") (pinfunction "1_1") (pintype "passive"))
      (node (ref "T8") (pin "1") (pinfunction "G_1") (pintype "passive"))
    )
    (net (code "29") (name "Net-(D23-A1)") (class "Default")
      (node (ref "C70") (pin "2") (pinfunction "2_2") (pintype "passive"))
      (node (ref "D23") (pin "1") (pinfunction "A1_1") (pintype "passive"))
      (node (ref "T9") (pin "21") (pinfunction "Sec1+_21") (pintype "passive"))
      (node (ref "T9") (pin "22") (pinfunction "Sec1+_22") (pintype "passive"))
    )
    (net (code "30") (name "Net-(D23-A2)") (class "Default")
      (node (ref "C59") (pin "2") (pinfunction "2_2") (pintype "passive"))
      (node (ref "D23") (pin "3") (pinfunction "A2_3") (pintype "passive"))
      (node (ref "T9") (pin "12") (pinfunction "Sec2+_12") (pintype "passive"))
      (node (ref "T9") (pin "13") (pinfunction "Sec2+_13") (pintype "passive"))
    )
    (net (code "31") (name "Net-(D23-K)") (class "Default")
      (node (ref "D23") (pin "2") (pinfunction "K_2") (pintype "passive"))
      (node (ref "L8") (pin "1") (pinfunction "1_1") (pintype "passive"))
    )
    (net (code "32") (name "Net-(D25-A)") (class "Default")
      (node (ref "D25") (pin "1") (pinfunction "A_1") (pintype "passive"))
      (node (ref "R89") (pin "1") (pinfunction "1_1") (pintype "passive"))
      (node (ref "R91") (pin "1") (pinfunction "1_1") (pintype "passive"))
      (node (ref "T10") (pin "1") (pinfunction "G_1") (pintype "passive"))
    )
    (net (code "33") (name "Net-(D26-A)") (class "Default")
      (node (ref "D26") (pin "1") (pinfunction "A_1") (pintype "passive"))
      (node (ref "R90") (pin "2") (pinfunction "2_2") (pintype "passive"))
      (node (ref "R92") (pin "2") (pinfunction "2_2") (pintype "passive"))
      (node (ref "T11") (pin "1") (pinfunction "G_1") (pintype "passive"))
    )
    (net (code "34") (name "Net-(D27-C)") (class "Default")
      (node (ref "D27") (pin "3") (pinfunction "C_3") (pintype "passive"))
      (node (ref "T12") (pin "3") (pinfunction "Sec2+_3") (pintype "passive"))
    )
    (net (code "35") (name "Net-(D29-C)") (class "Default")
      (node (ref "D29") (pin "3") (pinfunction "C_3") (pintype "passive"))
      (node (ref "T12") (pin "1") (pinfunction "Sec1+_1") (pintype "passive"))
    )
    (net (code "36") (name "Net-(D30-PadA)") (class "Default")
      (node (ref "D30") (pin "A") (pinfunction "A_A") (pintype "passive"))
      (node (ref "R96") (pin "2") (pinfunction "2_2") (pintype "passive"))
    )
    (net (code "37") (name "Net-(D36-PadA)") (class "Default")
      (node (ref "D36") (pin "A") (pinfunction "A_A") (pintype "passive"))
      (node (ref "R112") (pin "2") (pinfunction "2_2") (pintype "passive"))
    )
    (net (code "38") (name "Net-(L10-Pad1)") (class "Default")
      (node (ref "L10") (pin "1") (pinfunction "1_1") (pintype "passive"))
      (node (ref "P8") (pin "1") (pinfunction "1_1") (pintype "passive"))
      (node (ref "P8") (pin "2") (pinfunction "2_2") (pintype "passive"))
      (node (ref "T9") (pin "1") (pinfunction "Pri+_1") (pintype "passive"))
      (node (ref "T9") (pin "2") (pinfunction "Pri+_2") (pintype "passive"))
    )
    (net (code "39") (name "Net-(R81-Pad2)") (class "Default")
      (node (ref "R81") (pin "2") (pinfunction "2_2") (pintype "passive"))
      (node (ref "U11") (pin "2") (pinfunction "2_2") (pintype "passive"))
    )
    (net (code "40") (name "Net-(R82-Pad2)") (class "Default")
      (node (ref "R82") (pin "2") (pinfunction "2_2") (pintype "passive"))
      (node (ref "R86") (pin "1") (pinfunction "1_1") (pintype "passive"))
    )
    (net (code "41") (name "Net-(R86-Pad2)") (class "Default")
      (node (ref "R86") (pin "2") (pinfunction "2_2") (pintype "passive"))
      (node (ref "R88") (pin "1") (pinfunction "1_1") (pintype "passive"))
    )
    (net (code "42") (name "Net-(R93-Pad1)") (class "Default")
      (node (ref "R93") (pin "1") (pinfunction "1_1") (pintype "passive"))
      (node (ref "RP1") (pin "1") (pinfunction "1_1") (pintype "passive"))
      (node (ref "RP1") (pin "2") (pinfunction "2_2") (pintype "passive"))
    )
    (net (code "43") (name "Net-(T9-Pri+-Pad4)") (class "Default")
      (node (ref "T9") (pin "3") (pinfunction "Pri-_3") (pintype "passive"))
      (node (ref "T9") (pin "4") (pinfunction "Pri+_4") (pintype "passive"))
      (node (ref "T9") (pin "8") (pinfunction "Pri+_8") (pintype "passive"))
      (node (ref "T9") (pin "9") (pinfunction "Pri+_9") (pintype "passive"))
    )
    (net (code "44") (name "Net-(T12-Pri+)") (class "Default")
      (node (ref "T12") (pin "8") (pinfunction "Pri+_8") (pintype "passive"))
      (node (ref "T9") (pin "10") (pinfunction "Pri-_10") (pintype "passive"))
      (node (ref "T9") (pin "11") (pinfunction "Pri+_11") (pintype "passive"))
    )
    (net (code "45") (name "Net-(U9-VIN+)") (class "Default")
      (node (ref "C80") (pin "2") (pinfunction "2_2") (pintype "passive"))
      (node (ref "R87") (pin "1") (pinfunction "1_1") (pintype "passive"))
      (node (ref "U9") (pin "3") (pinfunction "VIN+_3") (pintype "input"))
    )
    (net (code "46") (name "Net-(U9-VIN-)") (class "Default")
      (node (ref "C76") (pin "2") (pinfunction "2_2") (pintype "passive"))
      (node (ref "R83") (pin "1") (pinfunction "1_1") (pintype "passive"))
      (node (ref "U11") (pin "3") (pinfunction "3_3") (pintype "passive"))
      (node (ref "U9") (pin "2") (pinfunction "VIN-_2") (pintype "input"))
    )
    (net (code "47") (name "Net-(U9-VOUT)") (class "Default")
      (node (ref "C76") (pin "1") (pinfunction "1_1") (pintype "passive"))
      (node (ref "U11") (pin "1") (pinfunction "1_1") (pintype "passive"))
      (node (ref "U9") (pin "6") (pinfunction "VOUT_6") (pintype "output"))
    )
    (net (code "48") (name "Net-(U11-O2)") (class "Default")
      (node (ref "C74") (pin "2") (pinfunction "2_2") (pintype "passive"))
      (node (ref "R84") (pin "2") (pinfunction "2_2") (pintype "passive"))
      (node (ref "U11") (pin "6") (pinfunction "O2_6") (pintype "passive"))
      (node (ref "U12") (pin "2") (pinfunction "VIN-_2") (pintype "input"))
    )
    (net (code "49") (name "Net-(U12-VOUT)") (class "Default")
      (node (ref "C74") (pin "1") (pinfunction "1_1") (pintype "passive"))
      (node (ref "R84") (pin "1") (pinfunction "1_1") (pintype "passive"))
      (node (ref "R85") (pin "2") (pinfunction "2_2") (pintype "passive"))
      (node (ref "U12") (pin "6") (pinfunction "VOUT_6") (pintype "output"))
    )
    (net (code "50") (name "Net-(U14-VB)") (class "Default")
      (node (ref "C79") (pin "2") (pinfunction "2_2") (pintype "passive"))
      (node (ref "D30") (pin "K") (pinfunction "K_K") (pintype "passive"))
      (node (ref "U14") (pin "8") (pinfunction "VB_8") (pintype "power_in"))
    )
    (net (code "51") (name "Net-(U18-VB)") (class "Default")
      (node (ref "C85") (pin "2") (pinfunction "2_2") (pintype "passive"))
      (node (ref "D36") (pin "K") (pinfunction "K_K") (pintype "passive"))
      (node (ref "U18") (pin "8") (pinfunction "VB_8") (pintype "power_in"))
    )
    (net (code "52") (name "unconnected-(D21-NC-Pad2)") (class "Default")
      (node (ref "D21") (pin "2") (pinfunction "NC_2") (pintype "passive"))
    )
    (net (code "53") (name "unconnected-(D22-NC-Pad2)") (class "Default")
      (node (ref "D22") (pin "2") (pinfunction "NC_2") (pintype "passive"))
    )
    (net (code "54") (name "unconnected-(D25-NC-Pad2)") (class "Default")
      (node (ref "D25") (pin "2") (pinfunction "NC_2") (pintype "passive"))
    )
    (net (code "55") (name "unconnected-(D26-NC-Pad2)") (class "Default")
      (node (ref "D26") (pin "2") (pinfunction "NC_2") (pintype "passive"))
    )
    (net (code "56") (name "unconnected-(U9-NC-Pad1)") (class "Default")
      (node (ref "U9") (pin "1") (pinfunction "NC_1") (pintype "passive+no_connect"))
    )
    (net (code "57") (name "unconnected-(U9-NC-Pad5)") (class "Default")
      (node (ref "U9") (pin "5") (pinfunction "NC_5") (pintype "passive+no_connect"))
    )
    (net (code "58") (name "unconnected-(U9-NC-Pad8)") (class "Default")
      (node (ref "U9") (pin "8") (pinfunction "NC_8") (pintype "passive+no_connect"))
    )
    (net (code "59") (name "unconnected-(U11-O1-Pad7)") (class "Default")
      (node (ref "U11") (pin "7") (pinfunction "O1_7") (pintype "passive+no_connect"))
    )
    (net (code "60") (name "unconnected-(U11-Pad8)") (class "Default")
      (node (ref "U11") (pin "8") (pinfunction "8_8") (pintype "passive+no_connect"))
    )
    (net (code "61") (name "unconnected-(U12-NC-Pad1)") (class "Default")
      (node (ref "U12") (pin "1") (pinfunction "NC_1") (pintype "passive+no_connect"))
    )
    (net (code "62") (name "unconnected-(U12-NC-Pad5)") (class "Default")
      (node (ref "U12") (pin "5") (pinfunction "NC_5") (pintype "passive+no_connect"))
    )
    (net (code "63") (name "unconnected-(U12-NC-Pad8)") (class "Default")
      (node (ref "U12") (pin "8") (pinfunction "NC_8") (pintype "passive+no_connect"))
    )
  )
)
